# 5v_to_3_3v.net
KiCad netlist of a schematic drawn in Altium Designer
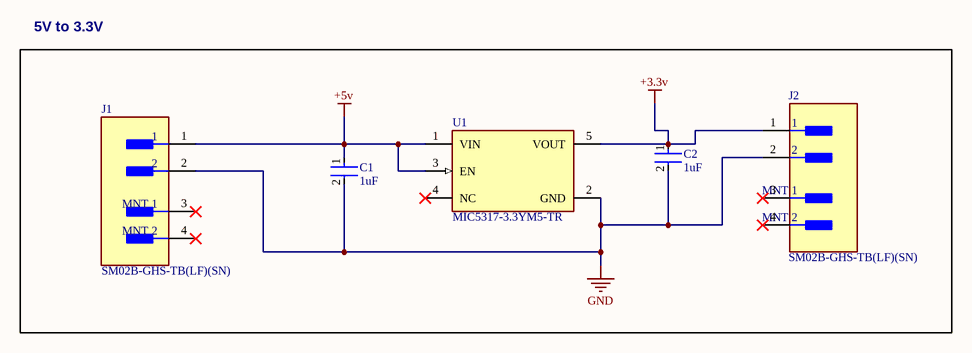
[diagram p0: 5v_to_3.3v.SchDoc]

(export (version "E")
  (design (tool "Eeschema 10.0.6"))
  (components
    (comp (ref "C1")
      (value "1uF")
      (footprint "FP-CC0805-0_85-MFG")
      (fields
        (field (name "MANUFACTURER") "Yageo")
        (field (name "OCTOPART") "https://octopart.com/cc0805kkx7r6bb105-yageo-42522859")
        (field (name "MANUFACTURER PART NUMBER") "CC0805KKX7R6BB105")
      )
      (libsource (lib "Altium Content Vault") (part "11868f565c42a9108669ba33697ecf6"))
    )
    (comp (ref "C2")
      (value "1uF")
      (footprint "FP-CC0805-0_85-MFG")
      (fields
        (field (name "MANUFACTURER") "Yageo")
        (field (name "OCTOPART") "https://octopart.com/cc0805kkx7r6bb105-yageo-42522859")
        (field (name "MANUFACTURER PART NUMBER") "CC0805KKX7R6BB105")
      )
      (libsource (lib "Altium Content Vault") (part "11868f565c42a9108669ba33697ecf6"))
    )
    (comp (ref "J1")
      (value "SM02B-GHS-TB(LF)(SN)")
      (footprint "FP-SM02B-GHS-TB_LF_SN-MFG")
      (description "CONN HEADER SMD R/A 2POS 1.25MM")
      (libsource (lib "Altium Content Vault") (part "56ec3178a87b3978bdc1b3682cd516a"))
    )
    (comp (ref "J2")
      (value "SM02B-GHS-TB(LF)(SN)")
      (footprint "FP-SM02B-GHS-TB_LF_SN-MFG")
      (description "CONN HEADER SMD R/A 2POS 1.25MM")
      (libsource (lib "") (part "56ec3178a87b3978bdc1b3682cd516a_1"))
    )
    (comp (ref "U1")
      (value "MIC5317-3.3YM5-TR")
      (footprint "FP-SOT23-5LD-PL-1-MFG")
      (description "IC REG LINEAR 3.3V 150MA SOT23-5")
      (libsource (lib "Altium Content Vault") (part "0a093dae7315cdc977fd108dde87457"))
    )
  )
  (nets
    (net (code "1") (name "+3.3v") (class "Default")
      (node (ref "C2") (pin "1") (pinfunction "1_1") (pintype "passive"))
      (node (ref "J2") (pin "1") (pinfunction "1_1") (pintype "passive"))
      (node (ref "U1") (pin "5") (pinfunction "VOUT_5") (pintype "power_in"))
    )
    (net (code "2") (name "+5v") (class "Default")
      (node (ref "C1") (pin "1") (pinfunction "1_1") (pintype "passive"))
      (node (ref "J1") (pin "1") (pinfunction "1_1") (pintype "passive"))
      (node (ref "U1") (pin "1") (pinfunction "VIN_1") (pintype "power_in"))
      (node (ref "U1") (pin "3") (pinfunction "EN_3") (pintype "input"))
    )
    (net (code "3") (name "GND") (class "Default")
      (node (ref "C1") (pin "2") (pinfunction "2_2") (pintype "passive"))
      (node (ref "C2") (pin "2") (pinfunction "2_2") (pintype "passive"))
      (node (ref "J1") (pin "2") (pinfunction "2_2") (pintype "passive"))
      (node (ref "J2") (pin "2") (pinfunction "2_2") (pintype "passive"))
      (node (ref "U1") (pin "2") (pinfunction "GND_2") (pintype "power_in"))
    )
    (net (code "4") (name "unconnected-(J1-MNT_1-Pad3)") (class "Default")
      (node (ref "J1") (pin "3") (pinfunction "MNT_1_3") (pintype "passive+no_connect"))
    )
    (net (code "5") (name "unconnected-(J1-MNT_2-Pad4)") (class "Default")
      (node (ref "J1") (pin "4") (pinfunction "MNT_2_4") (pintype "passive+no_connect"))
    )
    (net (code "6") (name "unconnected-(J2-MNT_1-Pad3)") (class "Default")
      (node (ref "J2") (pin "3") (pinfunction "MNT_1_3") (pintype "passive+no_connect"))
    )
    (net (code "7") (name "unconnected-(J2-MNT_2-Pad4)") (class "Default")
      (node (ref "J2") (pin "4") (pinfunction "MNT_2_4") (pintype "passive+no_connect"))
    )
    (net (code "8") (name "unconnected-(U1-NC-Pad4)") (class "Default")
      (node (ref "U1") (pin "4") (pinfunction "NC_4") (pintype "passive+no_connect"))
    )
  )
)
